# Reflex_InterfaceBoard_RevF_201603.net
KiCad netlist of a schematic drawn in Altium Designer
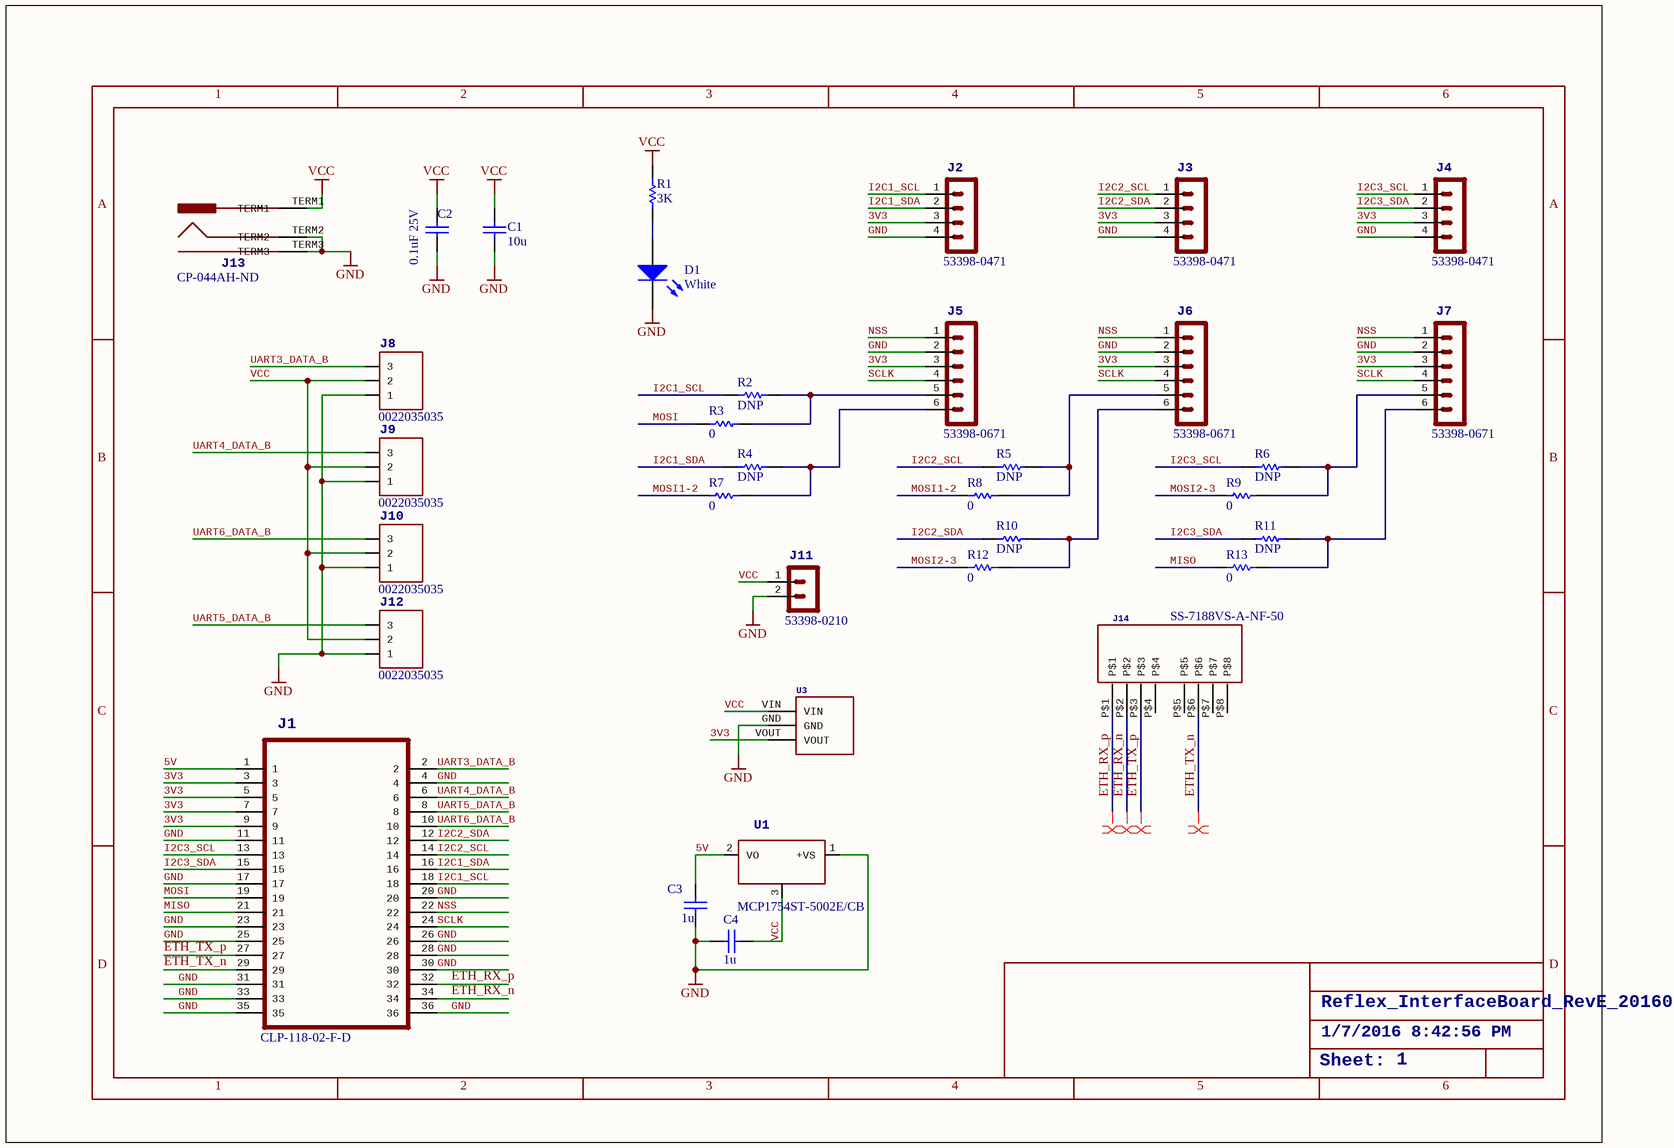
[diagram p0: Reflex_InterfaceBoard_RevF_201603.SchDoc]

(export (version "E")
  (design (tool "Eeschema 10.0.6"))
  (components
    (comp (ref "C1")
      (value "10u")
      (footprint "GENERIC_0603")
      (description "Capacitor")
      (fields
        (field (name "MANUFACTURER") "TDK Corporation")
        (field (name "MANUFACTURER PART NUMBER") "C1608X5R1E106M080AC")
      )
      (libsource (lib "RHR") (part "Cap_0603_10uF"))
    )
    (comp (ref "C2")
      (value "0.1uF 25V")
      (footprint "Generic_0603")
      (description "Capacitor 0.1uF 0603 package")
      (libsource (lib "RHR") (part "Cap_0603_0.1uF_25V"))
    )
    (comp (ref "C3")
      (value "1u")
      (footprint "Generic_0603")
      (description "Capacitor")
      (libsource (lib "RHR") (part "Cap_0603_1uF"))
    )
    (comp (ref "C4")
      (value "1u")
      (footprint "Generic_0603")
      (description "Capacitor")
      (libsource (lib "RHR") (part "Cap_0603_1uF"))
    )
    (comp (ref "D1")
      (value "White")
      (footprint "0402_LED_WHITE")
      (description "Surface mount LEDs")
      (fields (field (name "Comment") "LED White"))
      (libsource (lib "RHR") (part "LED_White_0402"))
    )
    (comp (ref "J1")
      (value "CLP-118-02-F-D")
      (footprint "SAMTEC_CLP-118-02-F-D")
      (description "SOCKET, 1.27MM, VERTICAL THT, 28WAY")
      (libsource (lib "Reflex_InterfaceBoard_RevE_201601") (part "CLP-118-02-F-D"))
    )
    (comp (ref "J2")
      (value "53398-0471")
      (footprint "53398-0410")
      (description "HEADER")
      (libsource (lib "RHR") (part "53398-0471"))
    )
    (comp (ref "J3")
      (value "53398-0471")
      (footprint "53398-0410")
      (description "HEADER")
      (libsource (lib "RHR") (part "53398-0471"))
    )
    (comp (ref "J4")
      (value "53398-0471")
      (footprint "53398-0410")
      (description "HEADER")
      (libsource (lib "RHR") (part "53398-0471"))
    )
    (comp (ref "J5")
      (value "53398-0671")
      (footprint "53398-0610")
      (description "HEADER")
      (libsource (lib "RHR") (part "53398-0671"))
    )
    (comp (ref "J6")
      (value "53398-0671")
      (footprint "53398-0610")
      (description "HEADER")
      (libsource (lib "RHR") (part "53398-0671"))
    )
    (comp (ref "J7")
      (value "53398-0671")
      (footprint "53398-0610")
      (description "HEADER")
      (libsource (lib "RHR") (part "53398-0671"))
    )
    (comp (ref "J8")
      (value "0022035035")
      (footprint "0022035035")
      (libsource (lib "RHR") (part "MOLEX_0022035035"))
    )
    (comp (ref "J9")
      (value "0022035035")
      (footprint "0022035035")
      (libsource (lib "RHR") (part "MOLEX_0022035035"))
    )
    (comp (ref "J10")
      (value "0022035035")
      (footprint "0022035035")
      (libsource (lib "RHR") (part "MOLEX_0022035035"))
    )
    (comp (ref "J11")
      (value "53398-0210")
      (footprint "53398-0210")
      (description "HEADER")
      (libsource (lib "RHR") (part "53398-0271"))
    )
    (comp (ref "J12")
      (value "0022035035")
      (footprint "0022035035")
      (libsource (lib "RHR") (part "MOLEX_0022035035"))
    )
    (comp (ref "J13")
      (value "CP-044AH-ND")
      (footprint "BRLJCK(DK:CP-044AH-ND)")
      (fields (field (name "Comment") "BRLJCK(DK:CP-044AH-ND)"))
      (libsource (lib "third-hand-library") (part "BRLJCK(DK{colon}CP-044AH-ND)"))
    )
    (comp (ref "J14")
      (value "SS-7188VS-A-NF-50")
      (footprint "STEWART-CONNECTOR-SS-7188VS-A-NF-50")
      (libsource (lib "third-hand-library") (part "SS-7188VS-A-NF-50"))
    )
    (comp (ref "R1")
      (value "3K")
      (footprint "Generic_0402")
      (description "Resistor 3 Kohm")
      (libsource (lib "RHR") (part "Res_0402_3.0K"))
    )
    (comp (ref "R2")
      (value "DNP")
      (footprint "Generic_0402")
      (description "Resistor 0402 DNP")
      (fields (field (name "Comment") "Res_0402_DNP"))
      (libsource (lib "RHR") (part "Res_0402_DNP"))
    )
    (comp (ref "R3")
      (value "0")
      (footprint "0402")
      (description "Resistor 0 ohm")
      (fields (field (name "Comment") "Res_0402_0"))
      (libsource (lib "RHR") (part "Res_0402_0"))
    )
    (comp (ref "R4")
      (value "DNP")
      (footprint "Generic_0402")
      (description "Resistor 0402 DNP")
      (fields (field (name "Comment") "Res_0402_DNP"))
      (libsource (lib "RHR") (part "Res_0402_DNP"))
    )
    (comp (ref "R5")
      (value "DNP")
      (footprint "Generic_0402")
      (description "Resistor 0402 DNP")
      (fields (field (name "Comment") "Res_0402_DNP"))
      (libsource (lib "RHR") (part "Res_0402_DNP"))
    )
    (comp (ref "R6")
      (value "DNP")
      (footprint "Generic_0402")
      (description "Resistor 0402 DNP")
      (fields (field (name "Comment") "Res_0402_DNP"))
      (libsource (lib "RHR") (part "Res_0402_DNP"))
    )
    (comp (ref "R7")
      (value "0")
      (footprint "0402")
      (description "Resistor 0 ohm")
      (fields (field (name "Comment") "Res_0402_0"))
      (libsource (lib "RHR") (part "Res_0402_0"))
    )
    (comp (ref "R8")
      (value "0")
      (footprint "0402")
      (description "Resistor 0 ohm")
      (fields (field (name "Comment") "Res_0402_0"))
      (libsource (lib "RHR") (part "Res_0402_0"))
    )
    (comp (ref "R9")
      (value "0")
      (footprint "0402")
      (description "Resistor 0 ohm")
      (fields (field (name "Comment") "Res_0402_0"))
      (libsource (lib "RHR") (part "Res_0402_0"))
    )
    (comp (ref "R10")
      (value "DNP")
      (footprint "Generic_0402")
      (description "Resistor 0402 DNP")
      (fields (field (name "Comment") "Res_0402_DNP"))
      (libsource (lib "RHR") (part "Res_0402_DNP"))
    )
    (comp (ref "R11")
      (value "DNP")
      (footprint "Generic_0402")
      (description "Resistor 0402 DNP")
      (fields (field (name "Comment") "Res_0402_DNP"))
      (libsource (lib "RHR") (part "Res_0402_DNP"))
    )
    (comp (ref "R12")
      (value "0")
      (footprint "0402")
      (description "Resistor 0 ohm")
      (fields (field (name "Comment") "Res_0402_0"))
      (libsource (lib "RHR") (part "Res_0402_0"))
    )
    (comp (ref "R13")
      (value "0")
      (footprint "0402")
      (description "Resistor 0 ohm")
      (fields (field (name "Comment") "Res_0402_0"))
      (libsource (lib "RHR") (part "Res_0402_0"))
    )
    (comp (ref "U1") (value "MCP1754ST-5002E/CB") (footprint "SOT-23") (libsource (lib "RHR") (part "LM50")))
    (comp (ref "U3")
      (value "945-1394-5-ND(DIGIKEY)")
      (footprint "945-1394-5-ND(DIGIKEY)")
      (libsource (lib "third-hand-library") (part "945-1394-5-ND(DIGIKEY)"))
    )
  )
  (nets
    (net (code "1") (name "/3V3") (class "Default")
      (node (ref "J1") (pin "3") (pinfunction "3_3") (pintype "passive"))
      (node (ref "J1") (pin "5") (pinfunction "5_5") (pintype "passive"))
      (node (ref "J1") (pin "7") (pinfunction "7_7") (pintype "passive"))
      (node (ref "J1") (pin "9") (pinfunction "9_9") (pintype "passive"))
      (node (ref "J2") (pin "3") (pinfunction "3_3") (pintype "passive"))
      (node (ref "J3") (pin "3") (pinfunction "3_3") (pintype "passive"))
      (node (ref "J4") (pin "3") (pinfunction "3_3") (pintype "passive"))
      (node (ref "J5") (pin "3") (pinfunction "3_3") (pintype "passive"))
      (node (ref "J6") (pin "3") (pinfunction "3_3") (pintype "passive"))
      (node (ref "J7") (pin "3") (pinfunction "3_3") (pintype "passive"))
      (node (ref "U3") (pin "VOUT") (pinfunction "VOUT_VOUT") (pintype "passive"))
    )
    (net (code "2") (name "/5V") (class "Default")
      (node (ref "C3") (pin "2") (pinfunction "2_2") (pintype "passive"))
      (node (ref "J1") (pin "1") (pinfunction "1_1") (pintype "passive"))
      (node (ref "U1") (pin "2") (pinfunction "VO_2") (pintype "passive"))
    )
    (net (code "3") (name "/ETH_RX_n") (class "Default")
      (node (ref "J1") (pin "34") (pinfunction "34_34") (pintype "passive"))
      (node (ref "J14") (pin "P$2") (pinfunction "P$2_P$2") (pintype "passive"))
    )
    (net (code "4") (name "/ETH_RX_p") (class "Default")
      (node (ref "J1") (pin "32") (pinfunction "32_32") (pintype "passive"))
      (node (ref "J14") (pin "P$1") (pinfunction "P$1_P$1") (pintype "passive"))
    )
    (net (code "5") (name "/ETH_TX_n") (class "Default")
      (node (ref "J1") (pin "29") (pinfunction "29_29") (pintype "passive"))
      (node (ref "J14") (pin "P$6") (pinfunction "P$6_P$6") (pintype "passive"))
    )
    (net (code "6") (name "/ETH_TX_p") (class "Default")
      (node (ref "J1") (pin "27") (pinfunction "27_27") (pintype "passive"))
      (node (ref "J14") (pin "P$3") (pinfunction "P$3_P$3") (pintype "passive"))
    )
    (net (code "7") (name "/I2C1_SCL") (class "Default")
      (node (ref "J1") (pin "18") (pinfunction "18_18") (pintype "passive"))
      (node (ref "J2") (pin "1") (pinfunction "1_1") (pintype "passive"))
      (node (ref "R2") (pin "1") (pinfunction "1_1") (pintype "passive"))
    )
    (net (code "8") (name "/I2C1_SDA") (class "Default")
      (node (ref "J1") (pin "16") (pinfunction "16_16") (pintype "passive"))
      (node (ref "J2") (pin "2") (pinfunction "2_2") (pintype "passive"))
      (node (ref "R4") (pin "1") (pinfunction "1_1") (pintype "passive"))
    )
    (net (code "9") (name "/I2C2_SCL") (class "Default")
      (node (ref "J1") (pin "14") (pinfunction "14_14") (pintype "passive"))
      (node (ref "J3") (pin "1") (pinfunction "1_1") (pintype "passive"))
      (node (ref "R5") (pin "1") (pinfunction "1_1") (pintype "passive"))
    )
    (net (code "10") (name "/I2C2_SDA") (class "Default")
      (node (ref "J1") (pin "12") (pinfunction "12_12") (pintype "passive"))
      (node (ref "J3") (pin "2") (pinfunction "2_2") (pintype "passive"))
      (node (ref "R10") (pin "1") (pinfunction "1_1") (pintype "passive"))
    )
    (net (code "11") (name "/I2C3_SCL") (class "Default")
      (node (ref "J1") (pin "13") (pinfunction "13_13") (pintype "passive"))
      (node (ref "J4") (pin "1") (pinfunction "1_1") (pintype "passive"))
      (node (ref "R6") (pin "1") (pinfunction "1_1") (pintype "passive"))
    )
    (net (code "12") (name "/I2C3_SDA") (class "Default")
      (node (ref "J1") (pin "15") (pinfunction "15_15") (pintype "passive"))
      (node (ref "J4") (pin "2") (pinfunction "2_2") (pintype "passive"))
      (node (ref "R11") (pin "1") (pinfunction "1_1") (pintype "passive"))
    )
    (net (code "13") (name "/MISO") (class "Default")
      (node (ref "J1") (pin "21") (pinfunction "21_21") (pintype "passive"))
      (node (ref "R13") (pin "1") (pinfunction "1_1") (pintype "passive"))
    )
    (net (code "14") (name "/MOSI") (class "Default")
      (node (ref "J1") (pin "19") (pinfunction "19_19") (pintype "passive"))
      (node (ref "R3") (pin "1") (pinfunction "1_1") (pintype "passive"))
    )
    (net (code "15") (name "/MOSI1-2") (class "Default")
      (node (ref "R7") (pin "1") (pinfunction "1_1") (pintype "passive"))
      (node (ref "R8") (pin "1") (pinfunction "1_1") (pintype "passive"))
    )
    (net (code "16") (name "/MOSI2-3") (class "Default")
      (node (ref "R12") (pin "1") (pinfunction "1_1") (pintype "passive"))
      (node (ref "R9") (pin "1") (pinfunction "1_1") (pintype "passive"))
    )
    (net (code "17") (name "/NSS") (class "Default")
      (node (ref "J1") (pin "22") (pinfunction "22_22") (pintype "passive"))
      (node (ref "J5") (pin "1") (pinfunction "1_1") (pintype "passive"))
      (node (ref "J6") (pin "1") (pinfunction "1_1") (pintype "passive"))
      (node (ref "J7") (pin "1") (pinfunction "1_1") (pintype "passive"))
    )
    (net (code "18") (name "/SCLK") (class "Default")
      (node (ref "J1") (pin "24") (pinfunction "24_24") (pintype "passive"))
      (node (ref "J5") (pin "4") (pinfunction "4_4") (pintype "passive"))
      (node (ref "J6") (pin "4") (pinfunction "4_4") (pintype "passive"))
      (node (ref "J7") (pin "4") (pinfunction "4_4") (pintype "passive"))
    )
    (net (code "19") (name "/UART3_DATA_B") (class "Default")
      (node (ref "J1") (pin "2") (pinfunction "2_2") (pintype "passive"))
      (node (ref "J8") (pin "1") (pinfunction "3_1") (pintype "passive"))
    )
    (net (code "20") (name "/UART4_DATA_B") (class "Default")
      (node (ref "J1") (pin "6") (pinfunction "6_6") (pintype "passive"))
      (node (ref "J9") (pin "1") (pinfunction "3_1") (pintype "passive"))
    )
    (net (code "21") (name "/UART5_DATA_B") (class "Default")
      (node (ref "J1") (pin "8") (pinfunction "8_8") (pintype "passive"))
      (node (ref "J12") (pin "1") (pinfunction "3_1") (pintype "passive"))
    )
    (net (code "22") (name "/UART6_DATA_B") (class "Default")
      (node (ref "J1") (pin "10") (pinfunction "10_10") (pintype "passive"))
      (node (ref "J10") (pin "1") (pinfunction "3_1") (pintype "passive"))
    )
    (net (code "23") (name "GND") (class "Default")
      (node (ref "C1") (pin "1") (pinfunction "1_1") (pintype "passive"))
      (node (ref "C2") (pin "1") (pinfunction "1_1") (pintype "passive"))
      (node (ref "C3") (pin "1") (pinfunction "1_1") (pintype "passive"))
      (node (ref "C4") (pin "2") (pinfunction "2_2") (pintype "passive"))
      (node (ref "D1") (pin "2") (pinfunction "K_2") (pintype "passive"))
      (node (ref "J1") (pin "11") (pinfunction "11_11") (pintype "passive"))
      (node (ref "J1") (pin "17") (pinfunction "17_17") (pintype "passive"))
      (node (ref "J1") (pin "20") (pinfunction "20_20") (pintype "passive"))
      (node (ref "J1") (pin "23") (pinfunction "23_23") (pintype "passive"))
      (node (ref "J1") (pin "25") (pinfunction "25_25") (pintype "passive"))
      (node (ref "J1") (pin "26") (pinfunction "26_26") (pintype "passive"))
      (node (ref "J1") (pin "28") (pinfunction "28_28") (pintype "passive"))
      (node (ref "J1") (pin "30") (pinfunction "30_30") (pintype "passive"))
      (node (ref "J1") (pin "31") (pinfunction "31_31") (pintype "passive"))
      (node (ref "J1") (pin "33") (pinfunction "33_33") (pintype "passive"))
      (node (ref "J1") (pin "35") (pinfunction "35_35") (pintype "passive"))
      (node (ref "J1") (pin "36") (pinfunction "36_36") (pintype "passive"))
      (node (ref "J1") (pin "4") (pinfunction "4_4") (pintype "passive"))
      (node (ref "J10") (pin "3") (pinfunction "1_3") (pintype "passive"))
      (node (ref "J11") (pin "2") (pinfunction "2_2") (pintype "passive"))
      (node (ref "J12") (pin "3") (pinfunction "1_3") (pintype "passive"))
      (node (ref "J13") (pin "TERM2") (pinfunction "TERM2_TERM2") (pintype "passive"))
      (node (ref "J13") (pin "TERM3") (pinfunction "TERM3_TERM3") (pintype "passive"))
      (node (ref "J2") (pin "4") (pinfunction "4_4") (pintype "passive"))
      (node (ref "J3") (pin "4") (pinfunction "4_4") (pintype "passive"))
      (node (ref "J4") (pin "4") (pinfunction "4_4") (pintype "passive"))
      (node (ref "J5") (pin "2") (pinfunction "2_2") (pintype "passive"))
      (node (ref "J6") (pin "2") (pinfunction "2_2") (pintype "passive"))
      (node (ref "J7") (pin "2") (pinfunction "2_2") (pintype "passive"))
      (node (ref "J8") (pin "3") (pinfunction "1_3") (pintype "passive"))
      (node (ref "J9") (pin "3") (pinfunction "1_3") (pintype "passive"))
      (node (ref "U1") (pin "1") (pinfunction "+VS_1") (pintype "passive"))
      (node (ref "U3") (pin "GND") (pinfunction "GND_GND") (pintype "passive"))
    )
    (net (code "24") (name "Net-(D1-A)") (class "Default")
      (node (ref "D1") (pin "1") (pinfunction "A_1") (pintype "passive"))
      (node (ref "R1") (pin "1") (pinfunction "1_1") (pintype "passive"))
    )
    (net (code "25") (name "Net-(J5-Pad5)") (class "Default")
      (node (ref "J5") (pin "5") (pinfunction "5_5") (pintype "passive"))
      (node (ref "R2") (pin "2") (pinfunction "2_2") (pintype "passive"))
      (node (ref "R3") (pin "2") (pinfunction "2_2") (pintype "passive"))
    )
    (net (code "26") (name "Net-(J5-Pad6)") (class "Default")
      (node (ref "J5") (pin "6") (pinfunction "6_6") (pintype "passive"))
      (node (ref "R4") (pin "2") (pinfunction "2_2") (pintype "passive"))
      (node (ref "R7") (pin "2") (pinfunction "2_2") (pintype "passive"))
    )
    (net (code "27") (name "Net-(J6-Pad5)") (class "Default")
      (node (ref "J6") (pin "5") (pinfunction "5_5") (pintype "passive"))
      (node (ref "R5") (pin "2") (pinfunction "2_2") (pintype "passive"))
      (node (ref "R8") (pin "2") (pinfunction "2_2") (pintype "passive"))
    )
    (net (code "28") (name "Net-(J6-Pad6)") (class "Default")
      (node (ref "J6") (pin "6") (pinfunction "6_6") (pintype "passive"))
      (node (ref "R10") (pin "2") (pinfunction "2_2") (pintype "passive"))
      (node (ref "R12") (pin "2") (pinfunction "2_2") (pintype "passive"))
    )
    (net (code "29") (name "Net-(J7-Pad5)") (class "Default")
      (node (ref "J7") (pin "5") (pinfunction "5_5") (pintype "passive"))
      (node (ref "R6") (pin "2") (pinfunction "2_2") (pintype "passive"))
      (node (ref "R9") (pin "2") (pinfunction "2_2") (pintype "passive"))
    )
    (net (code "30") (name "Net-(J7-Pad6)") (class "Default")
      (node (ref "J7") (pin "6") (pinfunction "6_6") (pintype "passive"))
      (node (ref "R11") (pin "2") (pinfunction "2_2") (pintype "passive"))
      (node (ref "R13") (pin "2") (pinfunction "2_2") (pintype "passive"))
    )
    (net (code "31") (name "VCC") (class "Default")
      (node (ref "C1") (pin "2") (pinfunction "2_2") (pintype "passive"))
      (node (ref "C2") (pin "2") (pinfunction "2_2") (pintype "passive"))
      (node (ref "C4") (pin "1") (pinfunction "1_1") (pintype "passive"))
      (node (ref "J10") (pin "2") (pinfunction "2_2") (pintype "passive"))
      (node (ref "J11") (pin "1") (pinfunction "1_1") (pintype "passive"))
      (node (ref "J12") (pin "2") (pinfunction "2_2") (pintype "passive"))
      (node (ref "J13") (pin "TERM1") (pinfunction "TERM1_TERM1") (pintype "passive"))
      (node (ref "J8") (pin "2") (pinfunction "2_2") (pintype "passive"))
      (node (ref "J9") (pin "2") (pinfunction "2_2") (pintype "passive"))
      (node (ref "R1") (pin "2") (pinfunction "2_2") (pintype "passive"))
      (node (ref "U1") (pin "3") (pinfunction "GND_3") (pintype "power_in"))
      (node (ref "U3") (pin "VIN") (pinfunction "VIN_VIN") (pintype "passive"))
    )
    (net (code "32") (name "unconnected-(J14-PadP$4)") (class "Default")
      (node (ref "J14") (pin "P$4") (pinfunction "P$4_P$4") (pintype "passive"))
    )
    (net (code "33") (name "unconnected-(J14-PadP$5)") (class "Default")
      (node (ref "J14") (pin "P$5") (pinfunction "P$5_P$5") (pintype "passive"))
    )
    (net (code "34") (name "unconnected-(J14-PadP$7)") (class "Default")
      (node (ref "J14") (pin "P$7") (pinfunction "P$7_P$7") (pintype "passive"))
    )
    (net (code "35") (name "unconnected-(J14-PadP$8)") (class "Default")
      (node (ref "J14") (pin "P$8") (pinfunction "P$8_P$8") (pintype "passive"))
    )
  )
)
